# LCMETER.net
KiCad netlist of a schematic drawn in EAGLE
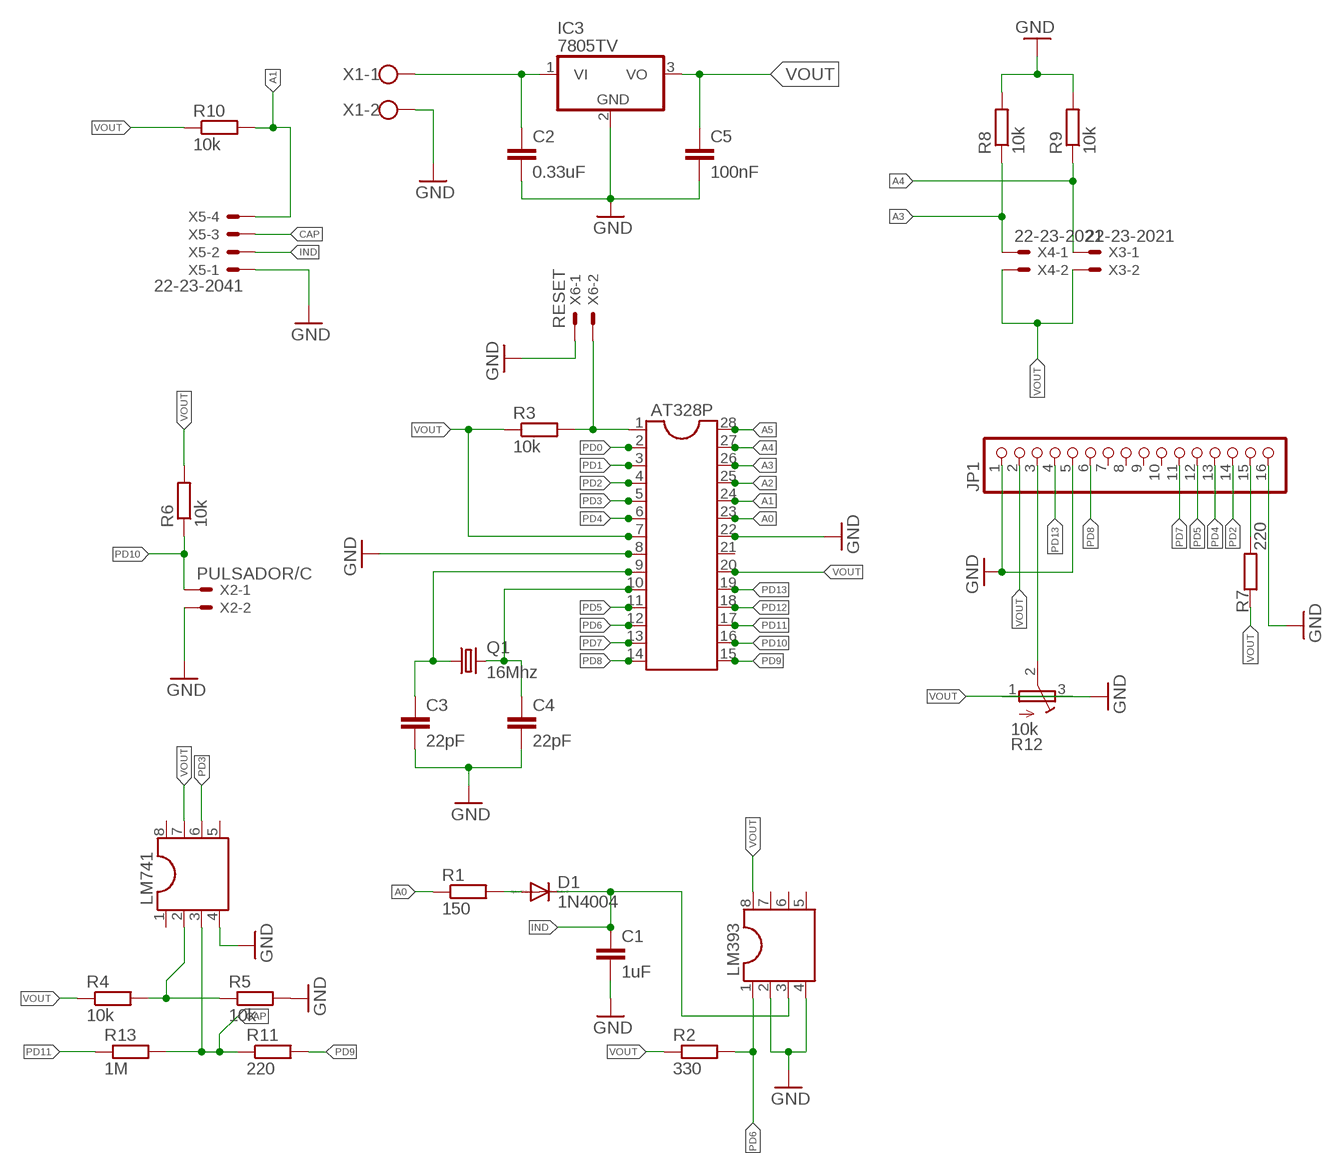
[diagram p0: schematic, sheet 1]

(export (version "E")
  (design (tool "Eeschema 10.0.6"))
  (components
    (comp (ref "AT328P")
      (value "DIL28-3")
      (footprint "eagle-import:DIL28-3")
      (libsource (lib "eagle-import") (part "DIL28-3"))
    )
    (comp (ref "C1")
      (value "1uF")
      (footprint "eagle-import:C050-024X044")
      (libsource (lib "eagle-import") (part "C-EU050-024X044"))
    )
    (comp (ref "C2")
      (value "0.33uF")
      (footprint "eagle-import:C050-024X044")
      (libsource (lib "eagle-import") (part "C-EU050-024X044"))
    )
    (comp (ref "C3")
      (value "22pF")
      (footprint "eagle-import:C025-030X050")
      (libsource (lib "eagle-import") (part "C-EU025-030X050"))
    )
    (comp (ref "C4")
      (value "22pF")
      (footprint "eagle-import:C025-030X050")
      (libsource (lib "eagle-import") (part "C-EU025-030X050"))
    )
    (comp (ref "C5")
      (value "100nF")
      (footprint "eagle-import:C025-030X050")
      (libsource (lib "eagle-import") (part "C-EU025-030X050"))
    )
    (comp (ref "D1")
      (value "1N4004")
      (footprint "eagle-import:DO41-10")
      (libsource (lib "eagle-import") (part "1N4004"))
    )
    (comp (ref "IC3")
      (value "7805TV")
      (footprint "eagle-import:TO220V")
      (libsource (lib "eagle-import") (part "78TV05"))
    )
    (comp (ref "JP1")
      (value "PINHD-1X16")
      (footprint "eagle-import:1X16")
      (libsource (lib "eagle-import") (part "PINHD-1X16"))
    )
    (comp (ref "LM393")
      (value "DIL8S")
      (footprint "eagle-import:SOCKET-08")
      (libsource (lib "eagle-import") (part "DIL8S"))
    )
    (comp (ref "LM741")
      (value "DIL8S")
      (footprint "eagle-import:SOCKET-08")
      (libsource (lib "eagle-import") (part "DIL8S"))
    )
    (comp (ref "Q1")
      (value "16Mhz")
      (footprint "eagle-import:HC49_S")
      (libsource (lib "eagle-import") (part "CRYSTALHC49S"))
    )
    (comp (ref "R1")
      (value "150")
      (footprint "eagle-import:0207_7")
      (libsource (lib "eagle-import") (part "R-EU_0207/7"))
    )
    (comp (ref "R2")
      (value "330")
      (footprint "eagle-import:0207_7")
      (libsource (lib "eagle-import") (part "R-EU_0207/7"))
    )
    (comp (ref "R3")
      (value "10k")
      (footprint "eagle-import:0207_7")
      (libsource (lib "eagle-import") (part "R-EU_0207/7"))
    )
    (comp (ref "R4")
      (value "10k")
      (footprint "eagle-import:0207_7")
      (libsource (lib "eagle-import") (part "R-EU_0207/7"))
    )
    (comp (ref "R5")
      (value "10k")
      (footprint "eagle-import:0207_7")
      (libsource (lib "eagle-import") (part "R-EU_0207/7"))
    )
    (comp (ref "R6")
      (value "10k")
      (footprint "eagle-import:0207_7")
      (libsource (lib "eagle-import") (part "R-EU_0207/7"))
    )
    (comp (ref "R7")
      (value "220")
      (footprint "eagle-import:0207_7")
      (libsource (lib "eagle-import") (part "R-EU_0207/7"))
    )
    (comp (ref "R8")
      (value "10k")
      (footprint "eagle-import:0207_7")
      (libsource (lib "eagle-import") (part "R-EU_0207/7"))
    )
    (comp (ref "R9")
      (value "10k")
      (footprint "eagle-import:0207_7")
      (libsource (lib "eagle-import") (part "R-EU_0207/7"))
    )
    (comp (ref "R10")
      (value "10k")
      (footprint "eagle-import:0207_7")
      (libsource (lib "eagle-import") (part "R-EU_0207/7"))
    )
    (comp (ref "R11")
      (value "220")
      (footprint "eagle-import:0207_7")
      (libsource (lib "eagle-import") (part "R-EU_0207/7"))
    )
    (comp (ref "R12")
      (value "10k")
      (footprint "eagle-import:RTRIM64W")
      (libsource (lib "eagle-import") (part "R-TRIMM64W"))
    )
    (comp (ref "R13")
      (value "1M")
      (footprint "eagle-import:0207_7")
      (libsource (lib "eagle-import") (part "R-EU_0207/7"))
    )
    (comp (ref "X1")
      (value "W237-102")
      (footprint "eagle-import:W237-102")
      (fields (field (name "MPN") "237-102"))
      (libsource (lib "eagle-import") (part "W237-102"))
    )
    (comp (ref "X2")
      (value "PULSADOR/C")
      (footprint "eagle-import:22-23-2021")
      (fields (field (name "MF") "MOLEX") (field (name "MPN") "22-23-2021"))
      (libsource (lib "eagle-import") (part "22-23-2021"))
    )
    (comp (ref "X3")
      (value "22-23-2021")
      (footprint "eagle-import:22-23-2021")
      (fields (field (name "MF") "MOLEX"))
      (libsource (lib "eagle-import") (part "22-23-2021"))
    )
    (comp (ref "X4")
      (value "22-23-2021")
      (footprint "eagle-import:22-23-2021")
      (fields (field (name "MF") "MOLEX"))
      (libsource (lib "eagle-import") (part "22-23-2021"))
    )
    (comp (ref "X5")
      (value "22-23-2041")
      (footprint "eagle-import:22-23-2041")
      (fields (field (name "MF") "MOLEX"))
      (libsource (lib "eagle-import") (part "22-23-2041"))
    )
    (comp (ref "X6")
      (value "RESET")
      (footprint "eagle-import:22-23-2021")
      (fields (field (name "MF") "MOLEX") (field (name "MPN") "22-23-2021"))
      (libsource (lib "eagle-import") (part "22-23-2021"))
    )
  )
  (nets
    (net (code "1") (name "A0") (class "Default")
      (node (ref "AT328P") (pin "23") (pinfunction "23_23") (pintype "passive"))
      (node (ref "R1") (pin "1") (pinfunction "1_1") (pintype "passive"))
    )
    (net (code "2") (name "A1") (class "Default")
      (node (ref "AT328P") (pin "24") (pinfunction "24_24") (pintype "passive"))
      (node (ref "R10") (pin "2") (pinfunction "2_2") (pintype "passive"))
      (node (ref "X5") (pin "4") (pinfunction "S_4") (pintype "passive"))
    )
    (net (code "3") (name "A2") (class "Default")
      (node (ref "AT328P") (pin "25") (pinfunction "25_25") (pintype "passive"))
    )
    (net (code "4") (name "A3") (class "Default")
      (node (ref "AT328P") (pin "26") (pinfunction "26_26") (pintype "passive"))
      (node (ref "R8") (pin "1") (pinfunction "1_1") (pintype "passive"))
      (node (ref "X4") (pin "1") (pinfunction "S_1") (pintype "passive"))
    )
    (net (code "5") (name "A4") (class "Default")
      (node (ref "AT328P") (pin "27") (pinfunction "27_27") (pintype "passive"))
      (node (ref "R9") (pin "1") (pinfunction "1_1") (pintype "passive"))
      (node (ref "X3") (pin "1") (pinfunction "S_1") (pintype "passive"))
    )
    (net (code "6") (name "A5") (class "Default")
      (node (ref "AT328P") (pin "28") (pinfunction "28_28") (pintype "passive"))
    )
    (net (code "7") (name "CAP") (class "Default")
      (node (ref "LM741") (pin "3") (pinfunction "3_3") (pintype "passive"))
      (node (ref "R11") (pin "1") (pinfunction "1_1") (pintype "passive"))
      (node (ref "R13") (pin "2") (pinfunction "2_2") (pintype "passive"))
      (node (ref "X5") (pin "3") (pinfunction "S_3") (pintype "passive"))
    )
    (net (code "8") (name "GND") (class "Default")
      (node (ref "AT328P") (pin "22") (pinfunction "22_22") (pintype "passive"))
      (node (ref "AT328P") (pin "8") (pinfunction "8_8") (pintype "passive"))
      (node (ref "C1") (pin "2") (pinfunction "2_2") (pintype "passive"))
      (node (ref "C2") (pin "2") (pinfunction "2_2") (pintype "passive"))
      (node (ref "C3") (pin "2") (pinfunction "2_2") (pintype "passive"))
      (node (ref "C4") (pin "2") (pinfunction "2_2") (pintype "passive"))
      (node (ref "C5") (pin "2") (pinfunction "2_2") (pintype "passive"))
      (node (ref "IC3") (pin "2") (pinfunction "GND_2") (pintype "passive"))
      (node (ref "JP1") (pin "1") (pinfunction "1_1") (pintype "passive"))
      (node (ref "JP1") (pin "16") (pinfunction "16_16") (pintype "passive"))
      (node (ref "JP1") (pin "5") (pinfunction "5_5") (pintype "passive"))
      (node (ref "LM393") (pin "2") (pinfunction "2_2") (pintype "passive"))
      (node (ref "LM393") (pin "4") (pinfunction "4_4") (pintype "passive"))
      (node (ref "LM741") (pin "4") (pinfunction "4_4") (pintype "passive"))
      (node (ref "R12") (pin "1") (pinfunction "A_1") (pintype "passive"))
      (node (ref "R5") (pin "2") (pinfunction "2_2") (pintype "passive"))
      (node (ref "R8") (pin "2") (pinfunction "2_2") (pintype "passive"))
      (node (ref "R9") (pin "2") (pinfunction "2_2") (pintype "passive"))
      (node (ref "X1") (pin "2") (pinfunction "KL_2") (pintype "passive"))
      (node (ref "X2") (pin "2") (pinfunction "S_2") (pintype "passive"))
      (node (ref "X5") (pin "1") (pinfunction "S_1") (pintype "passive"))
      (node (ref "X6") (pin "1") (pinfunction "S_1") (pintype "passive"))
    )
    (net (code "9") (name "IND") (class "Default")
      (node (ref "C1") (pin "1") (pinfunction "1_1") (pintype "passive"))
      (node (ref "D1") (pin "C") (pinfunction "C_C") (pintype "passive"))
      (node (ref "LM393") (pin "3") (pinfunction "3_3") (pintype "passive"))
      (node (ref "X5") (pin "2") (pinfunction "S_2") (pintype "passive"))
    )
    (net (code "10") (name "Net-(AT328P-Pad9)") (class "Default")
      (node (ref "AT328P") (pin "9") (pinfunction "9_9") (pintype "passive"))
      (node (ref "C3") (pin "1") (pinfunction "1_1") (pintype "passive"))
      (node (ref "Q1") (pin "1") (pinfunction "1_1") (pintype "passive"))
    )
    (net (code "11") (name "Net-(AT328P-Pad10)") (class "Default")
      (node (ref "AT328P") (pin "10") (pinfunction "10_10") (pintype "passive"))
      (node (ref "C4") (pin "1") (pinfunction "1_1") (pintype "passive"))
      (node (ref "Q1") (pin "2") (pinfunction "2_2") (pintype "passive"))
    )
    (net (code "12") (name "Net-(D1-PadA)") (class "Default")
      (node (ref "D1") (pin "A") (pinfunction "A_A") (pintype "passive"))
      (node (ref "R1") (pin "2") (pinfunction "2_2") (pintype "passive"))
    )
    (net (code "13") (name "Net-(IC3-VI)") (class "Default")
      (node (ref "C2") (pin "1") (pinfunction "1_1") (pintype "passive"))
      (node (ref "IC3") (pin "1") (pinfunction "VI_1") (pintype "input"))
      (node (ref "X1") (pin "1") (pinfunction "KL_1") (pintype "passive"))
    )
    (net (code "14") (name "Net-(JP1-Pad15)") (class "Default")
      (node (ref "JP1") (pin "15") (pinfunction "15_15") (pintype "passive"))
      (node (ref "R7") (pin "2") (pinfunction "2_2") (pintype "passive"))
    )
    (net (code "15") (name "Net-(LM741-Pad2)") (class "Default")
      (node (ref "LM741") (pin "2") (pinfunction "2_2") (pintype "passive"))
      (node (ref "R4") (pin "2") (pinfunction "2_2") (pintype "passive"))
      (node (ref "R5") (pin "1") (pinfunction "1_1") (pintype "passive"))
    )
    (net (code "16") (name "Net-(R12-S)") (class "Default")
      (node (ref "JP1") (pin "3") (pinfunction "3_3") (pintype "passive"))
      (node (ref "R12") (pin "2") (pinfunction "S_2") (pintype "passive"))
    )
    (net (code "17") (name "Net-(X6B-S)") (class "Default")
      (node (ref "AT328P") (pin "1") (pinfunction "1_1") (pintype "passive"))
      (node (ref "R3") (pin "2") (pinfunction "2_2") (pintype "passive"))
      (node (ref "X6") (pin "2") (pinfunction "S_2") (pintype "passive"))
    )
    (net (code "18") (name "PD0") (class "Default")
      (node (ref "AT328P") (pin "2") (pinfunction "2_2") (pintype "passive"))
    )
    (net (code "19") (name "PD1") (class "Default")
      (node (ref "AT328P") (pin "3") (pinfunction "3_3") (pintype "passive"))
    )
    (net (code "20") (name "PD2") (class "Default")
      (node (ref "AT328P") (pin "4") (pinfunction "4_4") (pintype "passive"))
      (node (ref "JP1") (pin "14") (pinfunction "14_14") (pintype "passive"))
    )
    (net (code "21") (name "PD3") (class "Default")
      (node (ref "AT328P") (pin "5") (pinfunction "5_5") (pintype "passive"))
      (node (ref "LM741") (pin "6") (pinfunction "6_6") (pintype "passive"))
    )
    (net (code "22") (name "PD4") (class "Default")
      (node (ref "AT328P") (pin "6") (pinfunction "6_6") (pintype "passive"))
      (node (ref "JP1") (pin "13") (pinfunction "13_13") (pintype "passive"))
    )
    (net (code "23") (name "PD5") (class "Default")
      (node (ref "AT328P") (pin "11") (pinfunction "11_11") (pintype "passive"))
      (node (ref "JP1") (pin "12") (pinfunction "12_12") (pintype "passive"))
    )
    (net (code "24") (name "PD6") (class "Default")
      (node (ref "AT328P") (pin "12") (pinfunction "12_12") (pintype "passive"))
      (node (ref "LM393") (pin "1") (pinfunction "1_1") (pintype "passive"))
      (node (ref "R2") (pin "2") (pinfunction "2_2") (pintype "passive"))
    )
    (net (code "25") (name "PD7") (class "Default")
      (node (ref "AT328P") (pin "13") (pinfunction "13_13") (pintype "passive"))
      (node (ref "JP1") (pin "11") (pinfunction "11_11") (pintype "passive"))
    )
    (net (code "26") (name "PD8") (class "Default")
      (node (ref "AT328P") (pin "14") (pinfunction "14_14") (pintype "passive"))
      (node (ref "JP1") (pin "6") (pinfunction "6_6") (pintype "passive"))
    )
    (net (code "27") (name "PD9") (class "Default")
      (node (ref "AT328P") (pin "15") (pinfunction "15_15") (pintype "passive"))
      (node (ref "R11") (pin "2") (pinfunction "2_2") (pintype "passive"))
    )
    (net (code "28") (name "PD10") (class "Default")
      (node (ref "AT328P") (pin "16") (pinfunction "16_16") (pintype "passive"))
      (node (ref "R6") (pin "1") (pinfunction "1_1") (pintype "passive"))
      (node (ref "X2") (pin "1") (pinfunction "S_1") (pintype "passive"))
    )
    (net (code "29") (name "PD11") (class "Default")
      (node (ref "AT328P") (pin "17") (pinfunction "17_17") (pintype "passive"))
      (node (ref "R13") (pin "1") (pinfunction "1_1") (pintype "passive"))
    )
    (net (code "30") (name "PD12") (class "Default")
      (node (ref "AT328P") (pin "18") (pinfunction "18_18") (pintype "passive"))
    )
    (net (code "31") (name "PD13") (class "Default")
      (node (ref "AT328P") (pin "19") (pinfunction "19_19") (pintype "passive"))
      (node (ref "JP1") (pin "4") (pinfunction "4_4") (pintype "passive"))
    )
    (net (code "32") (name "VOUT") (class "Default")
      (node (ref "AT328P") (pin "20") (pinfunction "20_20") (pintype "passive"))
      (node (ref "AT328P") (pin "7") (pinfunction "7_7") (pintype "passive"))
      (node (ref "C5") (pin "1") (pinfunction "1_1") (pintype "passive"))
      (node (ref "IC3") (pin "3") (pinfunction "VO_3") (pintype "passive"))
      (node (ref "JP1") (pin "2") (pinfunction "2_2") (pintype "passive"))
      (node (ref "LM393") (pin "8") (pinfunction "8_8") (pintype "passive"))
      (node (ref "LM741") (pin "7") (pinfunction "7_7") (pintype "passive"))
      (node (ref "R10") (pin "1") (pinfunction "1_1") (pintype "passive"))
      (node (ref "R12") (pin "3") (pinfunction "E_3") (pintype "passive"))
      (node (ref "R2") (pin "1") (pinfunction "1_1") (pintype "passive"))
      (node (ref "R3") (pin "1") (pinfunction "1_1") (pintype "passive"))
      (node (ref "R4") (pin "1") (pinfunction "1_1") (pintype "passive"))
      (node (ref "R6") (pin "2") (pinfunction "2_2") (pintype "passive"))
      (node (ref "R7") (pin "1") (pinfunction "1_1") (pintype "passive"))
      (node (ref "X3") (pin "2") (pinfunction "S_2") (pintype "passive"))
      (node (ref "X4") (pin "2") (pinfunction "S_2") (pintype "passive"))
    )
    (net (code "33") (name "unconnected-(AT328P-Pad21)") (class "Default")
      (node (ref "AT328P") (pin "21") (pinfunction "21_21") (pintype "passive"))
    )
    (net (code "34") (name "unconnected-(JP1-Pad7)") (class "Default")
      (node (ref "JP1") (pin "7") (pinfunction "7_7") (pintype "passive"))
    )
    (net (code "35") (name "unconnected-(JP1-Pad8)") (class "Default")
      (node (ref "JP1") (pin "8") (pinfunction "8_8") (pintype "passive"))
    )
    (net (code "36") (name "unconnected-(JP1-Pad9)") (class "Default")
      (node (ref "JP1") (pin "9") (pinfunction "9_9") (pintype "passive"))
    )
    (net (code "37") (name "unconnected-(JP1-Pad10)") (class "Default")
      (node (ref "JP1") (pin "10") (pinfunction "10_10") (pintype "passive"))
    )
    (net (code "38") (name "unconnected-(LM393-Pad5)") (class "Default")
      (node (ref "LM393") (pin "5") (pinfunction "5_5") (pintype "passive"))
    )
    (net (code "39") (name "unconnected-(LM393-Pad6)") (class "Default")
      (node (ref "LM393") (pin "6") (pinfunction "6_6") (pintype "passive"))
    )
    (net (code "40") (name "unconnected-(LM393-Pad7)") (class "Default")
      (node (ref "LM393") (pin "7") (pinfunction "7_7") (pintype "passive"))
    )
    (net (code "41") (name "unconnected-(LM741-Pad1)") (class "Default")
      (node (ref "LM741") (pin "1") (pinfunction "1_1") (pintype "passive"))
    )
    (net (code "42") (name "unconnected-(LM741-Pad5)") (class "Default")
      (node (ref "LM741") (pin "5") (pinfunction "5_5") (pintype "passive"))
    )
    (net (code "43") (name "unconnected-(LM741-Pad8)") (class "Default")
      (node (ref "LM741") (pin "8") (pinfunction "8_8") (pintype "passive"))
    )
  )
)
